# Espressomaschine.net
KiCad netlist of a schematic drawn in EAGLE
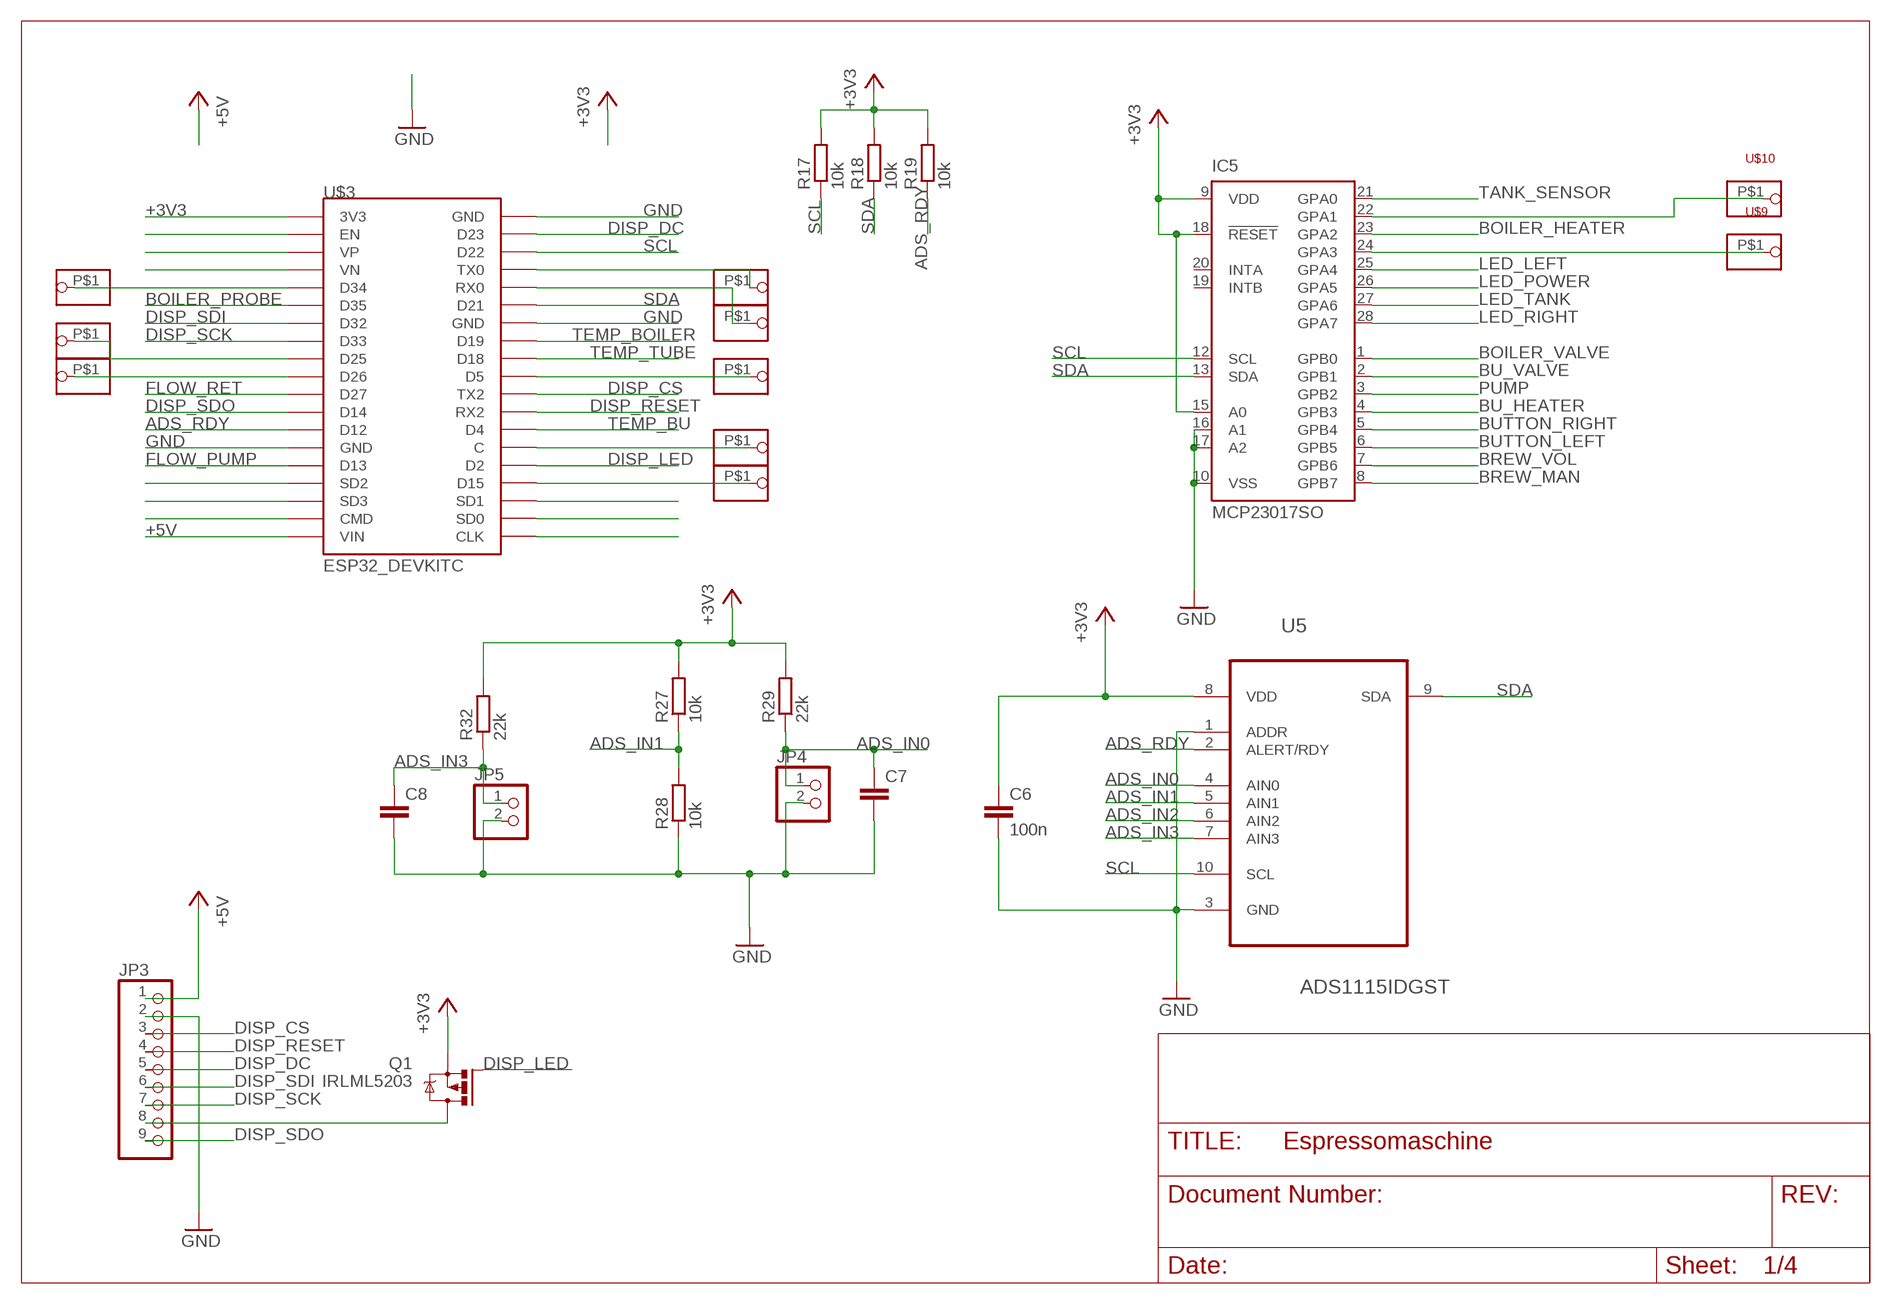
[diagram p0: schematic, sheet 1]
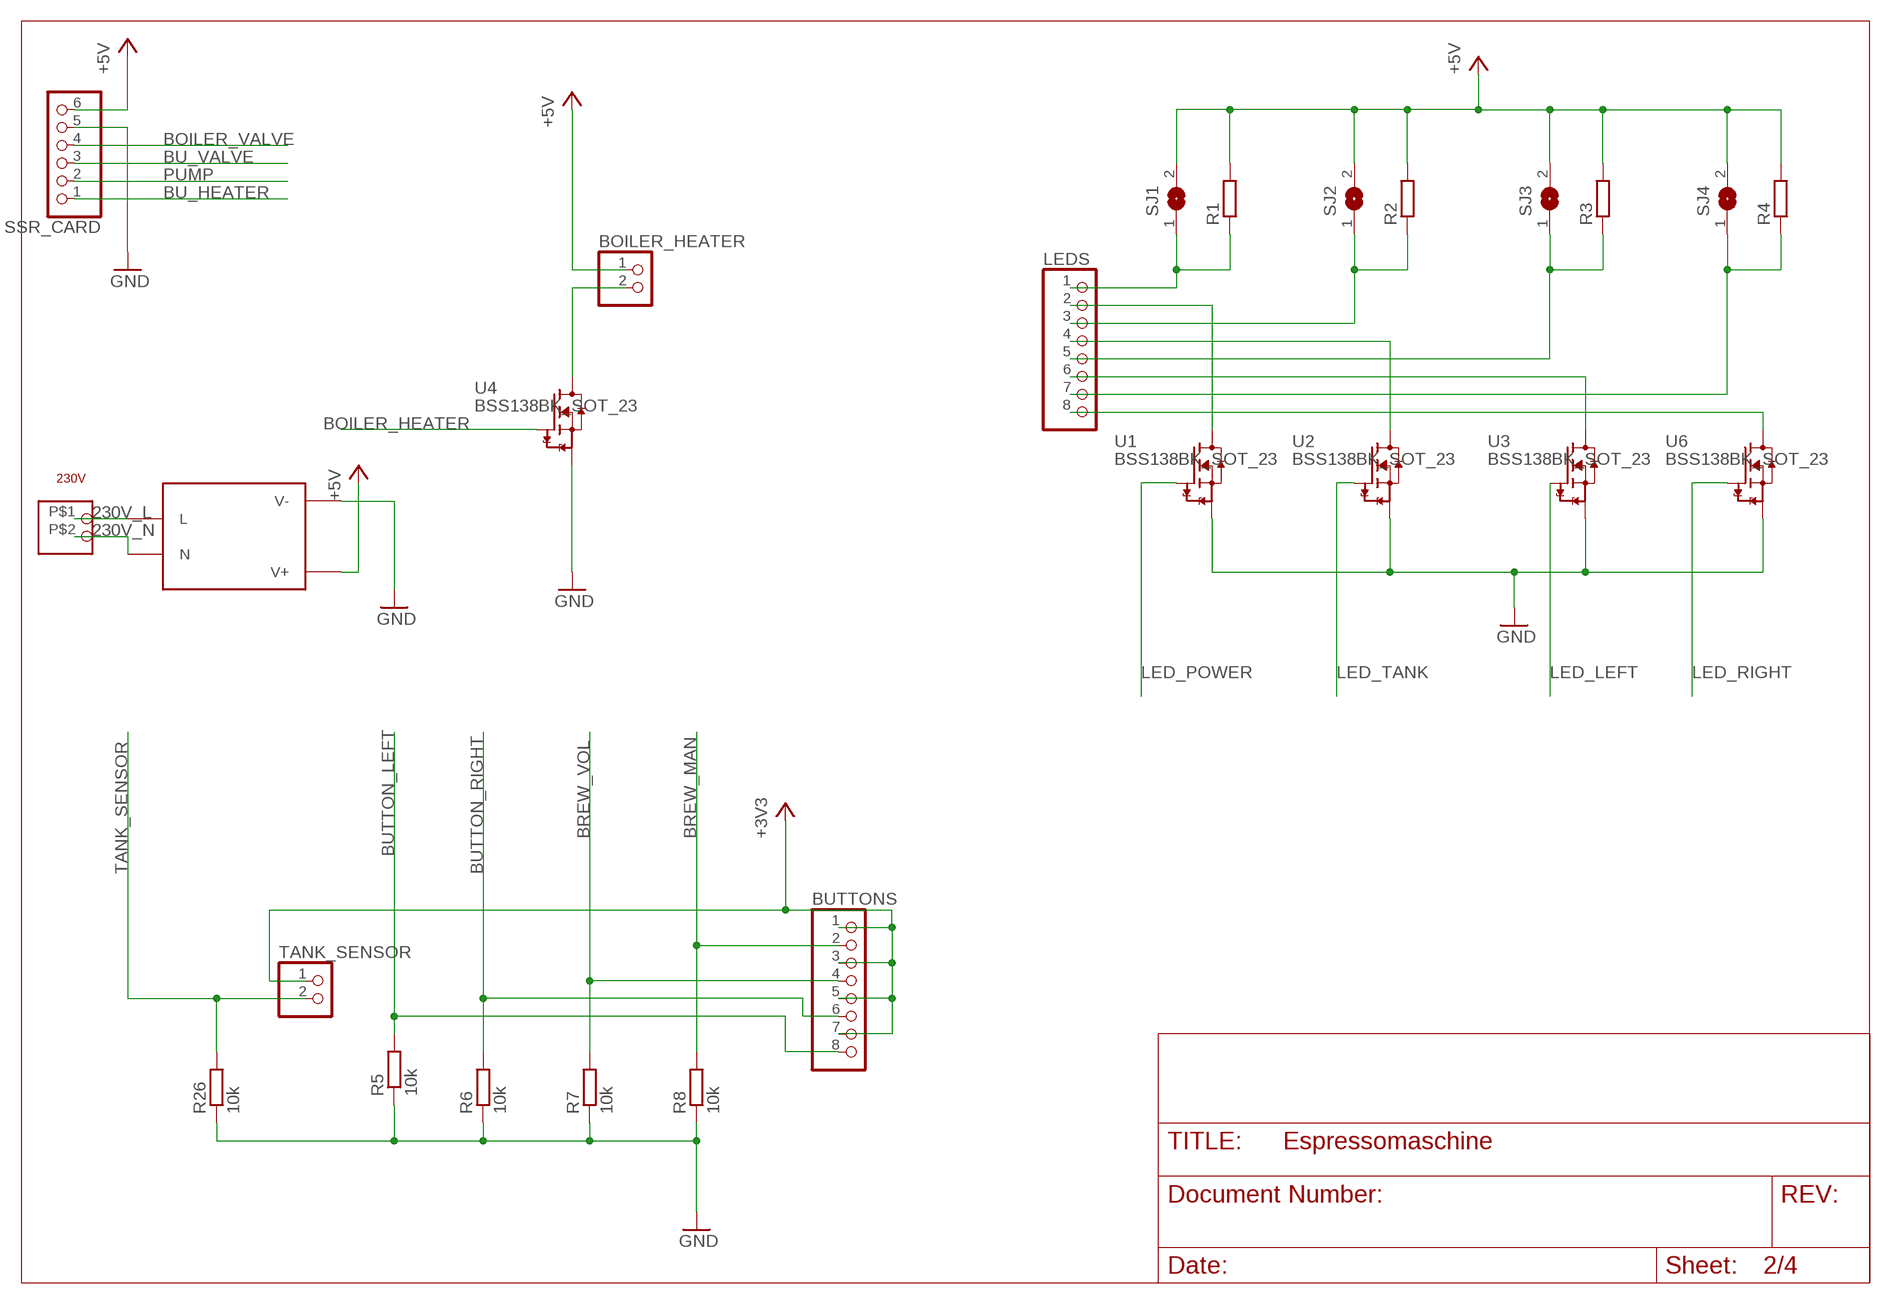
[diagram p1: schematic, sheet 2]
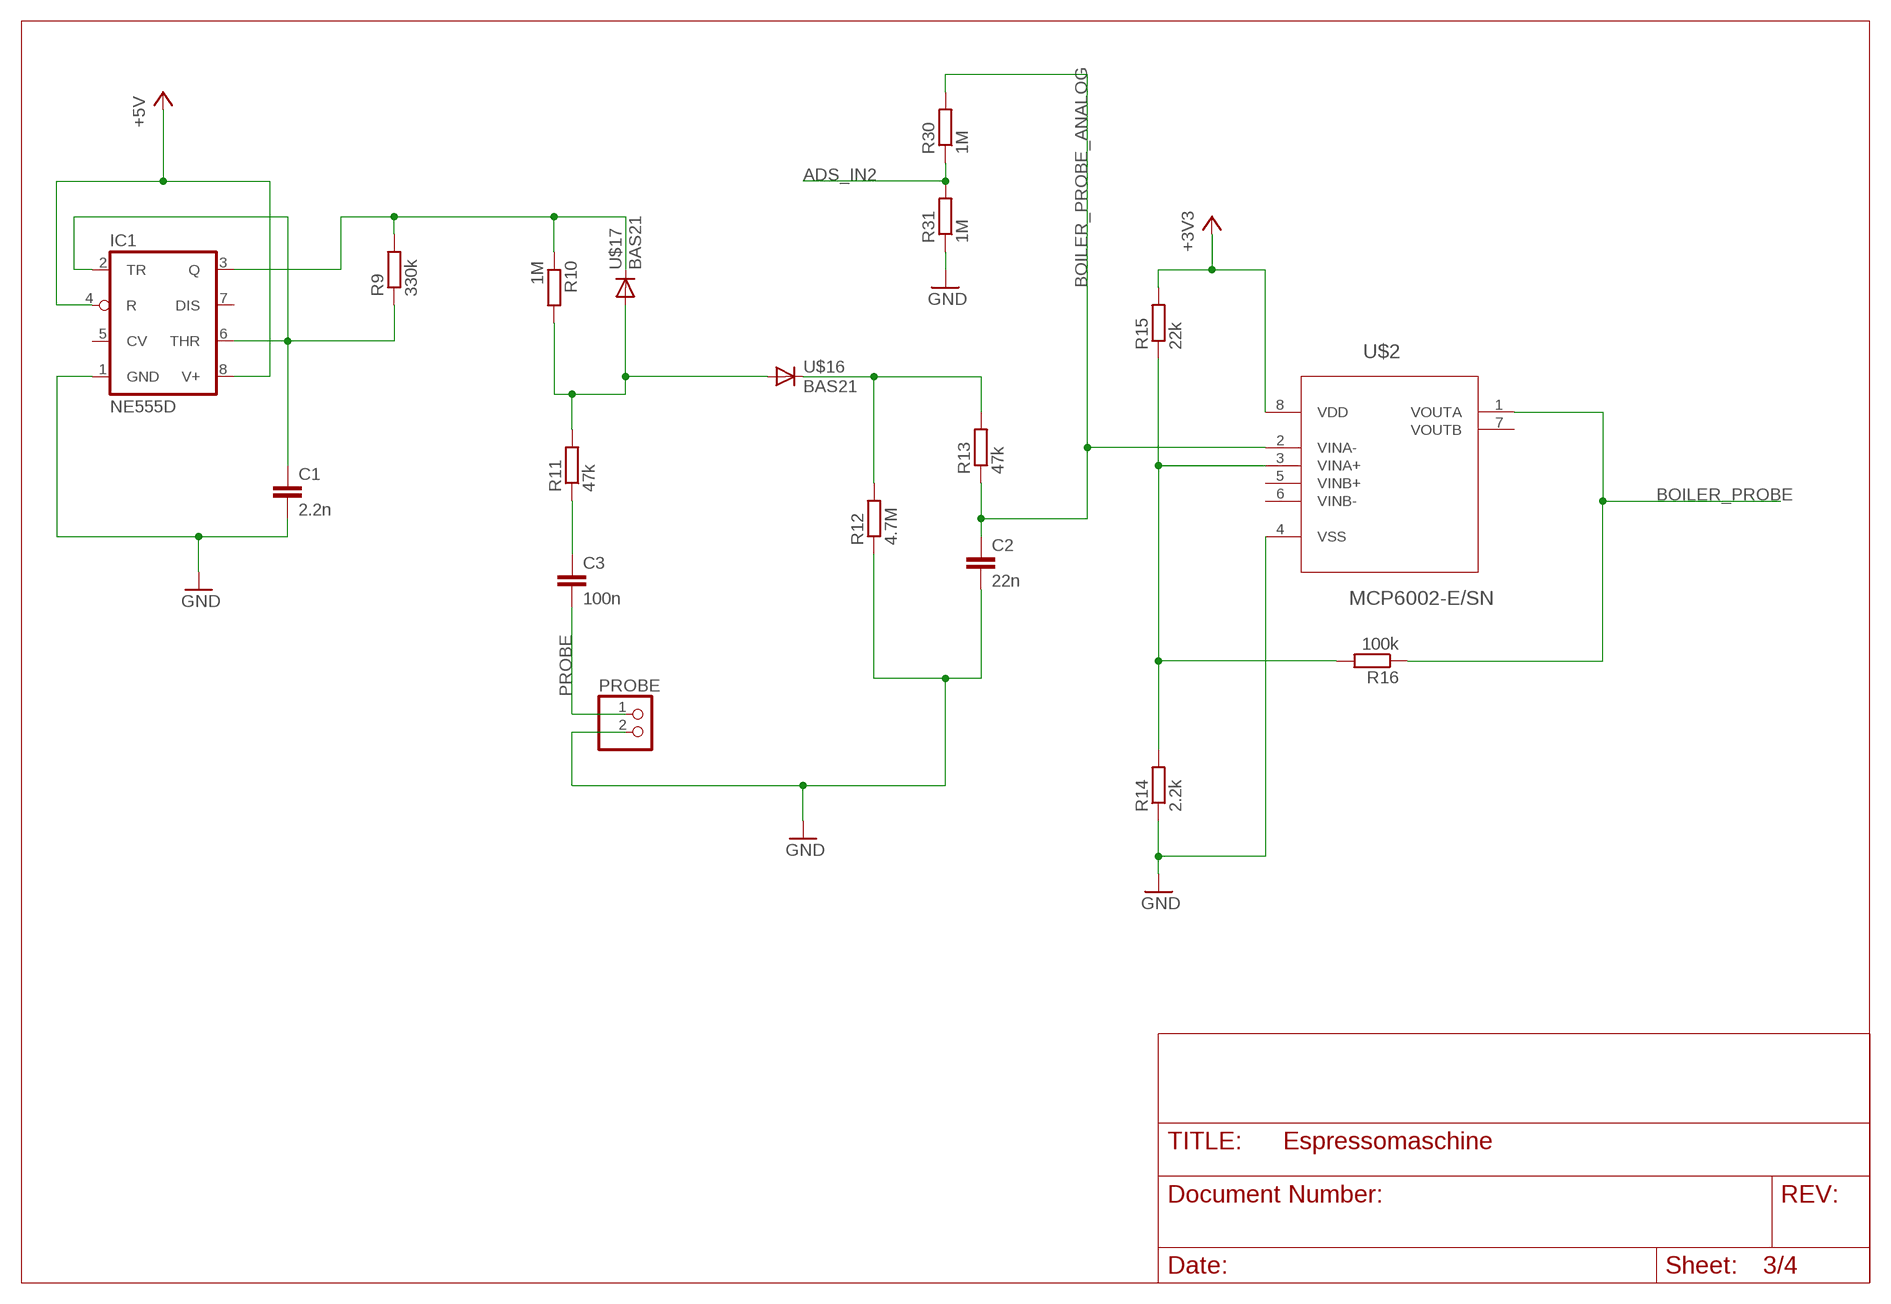
[diagram p2: schematic, sheet 3]
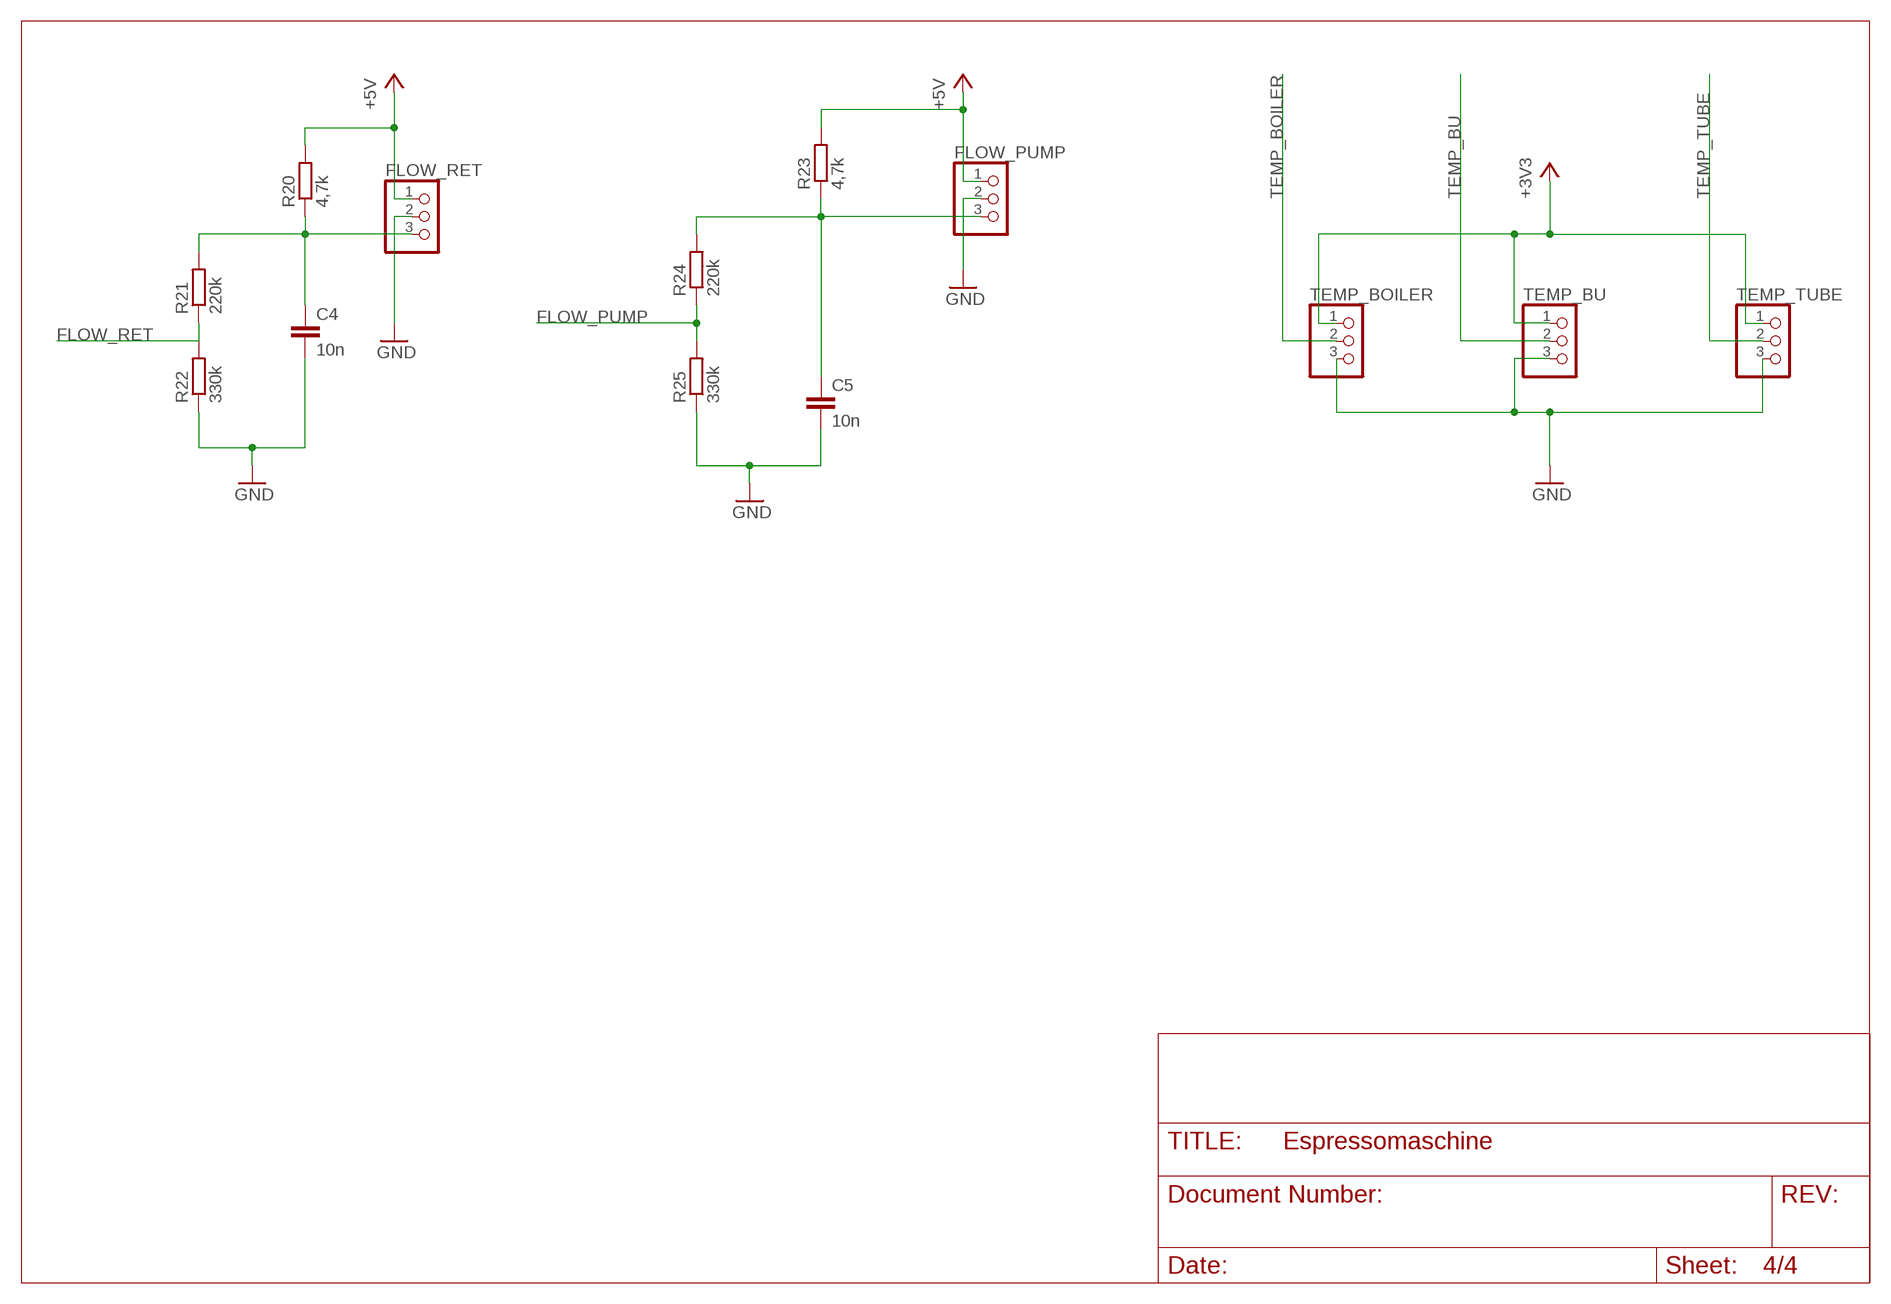
[diagram p3: schematic, sheet 4]

(export (version "E")
  (design (tool "Eeschema 10.0.6"))
  (components
    (comp (ref "230V")
      (value "1X2RM5")
      (footprint "eagle-import:1X02_RM5")
      (libsource (lib "eagle-import") (part "1X2RM5"))
    )
    (comp (ref "BOILER_HEATER")
      (value "PINHD-1X2")
      (footprint "eagle-import:1X02")
      (libsource (lib "eagle-import") (part "PINHD-1X2"))
    )
    (comp (ref "BUTTONS")
      (value "PINHD-1X8")
      (footprint "eagle-import:1X08")
      (libsource (lib "eagle-import") (part "PINHD-1X8"))
    )
    (comp (ref "LEDS")
      (value "PINHD-1X8")
      (footprint "eagle-import:1X08")
      (libsource (lib "eagle-import") (part "PINHD-1X8"))
    )
    (comp (ref "R1")
      (value "R-EU_R0603")
      (footprint "eagle-import:R0603")
      (libsource (lib "eagle-import") (part "R-EU_R0603"))
    )
    (comp (ref "R2")
      (value "R-EU_R0603")
      (footprint "eagle-import:R0603")
      (libsource (lib "eagle-import") (part "R-EU_R0603"))
    )
    (comp (ref "R3")
      (value "R-EU_R0603")
      (footprint "eagle-import:R0603")
      (libsource (lib "eagle-import") (part "R-EU_R0603"))
    )
    (comp (ref "R4")
      (value "R-EU_R0603")
      (footprint "eagle-import:R0603")
      (libsource (lib "eagle-import") (part "R-EU_R0603"))
    )
    (comp (ref "R5")
      (value "10k")
      (footprint "eagle-import:R0603")
      (libsource (lib "eagle-import") (part "R-EU_R0603"))
    )
    (comp (ref "R6")
      (value "10k")
      (footprint "eagle-import:R0603")
      (libsource (lib "eagle-import") (part "R-EU_R0603"))
    )
    (comp (ref "R7")
      (value "10k")
      (footprint "eagle-import:R0603")
      (libsource (lib "eagle-import") (part "R-EU_R0603"))
    )
    (comp (ref "R8")
      (value "10k")
      (footprint "eagle-import:R0603")
      (libsource (lib "eagle-import") (part "R-EU_R0603"))
    )
    (comp (ref "R26")
      (value "10k")
      (footprint "eagle-import:R0603")
      (libsource (lib "eagle-import") (part "R-EU_R0603"))
    )
    (comp (ref "SJ1") (value "SJ") (footprint "eagle-import:SJ") (libsource (lib "eagle-import") (part "SJ")))
    (comp (ref "SJ2") (value "SJ") (footprint "eagle-import:SJ") (libsource (lib "eagle-import") (part "SJ")))
    (comp (ref "SJ3") (value "SJ") (footprint "eagle-import:SJ") (libsource (lib "eagle-import") (part "SJ")))
    (comp (ref "SJ4") (value "SJ") (footprint "eagle-import:SJ") (libsource (lib "eagle-import") (part "SJ")))
    (comp (ref "SSR_CARD")
      (value "PINHD-1X6")
      (footprint "eagle-import:1X06")
      (libsource (lib "eagle-import") (part "PINHD-1X6"))
    )
    (comp (ref "TANK_SENSOR")
      (value "PINHD-1X2")
      (footprint "eagle-import:1X02")
      (libsource (lib "eagle-import") (part "PINHD-1X2"))
    )
    (comp (ref "U$1")
      (value "HLK-PM0X")
      (footprint "eagle-import:HLK-PM0X")
      (libsource (lib "eagle-import") (part "HLK-PM0X"))
    )
    (comp (ref "U1")
      (value "BSS138BK_SOT_23")
      (footprint "eagle-import:SOT23")
      (libsource (lib "eagle-import") (part "BSS138BK_SOT_23"))
    )
    (comp (ref "U2")
      (value "BSS138BK_SOT_23")
      (footprint "eagle-import:SOT23")
      (libsource (lib "eagle-import") (part "BSS138BK_SOT_23"))
    )
    (comp (ref "U3")
      (value "BSS138BK_SOT_23")
      (footprint "eagle-import:SOT23")
      (libsource (lib "eagle-import") (part "BSS138BK_SOT_23"))
    )
    (comp (ref "U4")
      (value "BSS138BK_SOT_23")
      (footprint "eagle-import:SOT23")
      (libsource (lib "eagle-import") (part "BSS138BK_SOT_23"))
    )
    (comp (ref "U6")
      (value "BSS138BK_SOT_23")
      (footprint "eagle-import:SOT23")
      (libsource (lib "eagle-import") (part "BSS138BK_SOT_23"))
    )
    (comp (ref "C1")
      (value "2.2n")
      (footprint "eagle-import:C0603")
      (libsource (lib "eagle-import") (part "C-EUC0603"))
    )
    (comp (ref "C2")
      (value "22n")
      (footprint "eagle-import:C0603")
      (libsource (lib "eagle-import") (part "C-EUC0603"))
    )
    (comp (ref "C3")
      (value "100n")
      (footprint "eagle-import:C0603")
      (libsource (lib "eagle-import") (part "C-EUC0603"))
    )
    (comp (ref "IC1")
      (value "NE555D")
      (footprint "eagle-import:SO08")
      (libsource (lib "eagle-import") (part "555DNE"))
    )
    (comp (ref "PROBE")
      (value "PINHD-1X2")
      (footprint "eagle-import:1X02")
      (libsource (lib "eagle-import") (part "PINHD-1X2"))
    )
    (comp (ref "R9")
      (value "330k")
      (footprint "eagle-import:R0603")
      (libsource (lib "eagle-import") (part "R-EU_R0603"))
    )
    (comp (ref "R10")
      (value "1M")
      (footprint "eagle-import:R0603")
      (libsource (lib "eagle-import") (part "R-EU_R0603"))
    )
    (comp (ref "R11")
      (value "47k")
      (footprint "eagle-import:R0603")
      (libsource (lib "eagle-import") (part "R-EU_R0603"))
    )
    (comp (ref "R12")
      (value "4.7M")
      (footprint "eagle-import:R0603")
      (libsource (lib "eagle-import") (part "R-EU_R0603"))
    )
    (comp (ref "R13")
      (value "47k")
      (footprint "eagle-import:R0603")
      (libsource (lib "eagle-import") (part "R-EU_R0603"))
    )
    (comp (ref "R14")
      (value "2.2k")
      (footprint "eagle-import:R0603")
      (libsource (lib "eagle-import") (part "R-EU_R0603"))
    )
    (comp (ref "R15")
      (value "22k")
      (footprint "eagle-import:R0603")
      (libsource (lib "eagle-import") (part "R-EU_R0603"))
    )
    (comp (ref "R16")
      (value "100k")
      (footprint "eagle-import:R0603")
      (libsource (lib "eagle-import") (part "R-EU_R0603"))
    )
    (comp (ref "R30")
      (value "1M")
      (footprint "eagle-import:R0603")
      (libsource (lib "eagle-import") (part "R-EU_R0603"))
    )
    (comp (ref "R31")
      (value "1M")
      (footprint "eagle-import:R0603")
      (libsource (lib "eagle-import") (part "R-EU_R0603"))
    )
    (comp (ref "U$2")
      (value "MCP6002-E/SN")
      (footprint "eagle-import:SOIC127P600X175-8N")
      (libsource (lib "eagle-import") (part "MCP6002-E/SN"))
    )
    (comp (ref "U$16")
      (value "BAS21")
      (footprint "eagle-import:SOT23")
      (libsource (lib "eagle-import") (part "BAS21"))
    )
    (comp (ref "U$17")
      (value "BAS21")
      (footprint "eagle-import:SOT23")
      (libsource (lib "eagle-import") (part "BAS21"))
    )
    (comp (ref "C4")
      (value "10n")
      (footprint "eagle-import:C0603")
      (libsource (lib "eagle-import") (part "C-EUC0603"))
    )
    (comp (ref "C5")
      (value "10n")
      (footprint "eagle-import:C0603")
      (libsource (lib "eagle-import") (part "C-EUC0603"))
    )
    (comp (ref "FLOW_PUMP")
      (value "PINHD-1X3")
      (footprint "eagle-import:1X03")
      (libsource (lib "eagle-import") (part "PINHD-1X3"))
    )
    (comp (ref "FLOW_RET")
      (value "PINHD-1X3")
      (footprint "eagle-import:1X03")
      (libsource (lib "eagle-import") (part "PINHD-1X3"))
    )
    (comp (ref "R20")
      (value "4,7k")
      (footprint "eagle-import:R0603")
      (libsource (lib "eagle-import") (part "R-EU_R0603"))
    )
    (comp (ref "R21")
      (value "220k")
      (footprint "eagle-import:R0603")
      (libsource (lib "eagle-import") (part "R-EU_R0603"))
    )
    (comp (ref "R22")
      (value "330k")
      (footprint "eagle-import:R0603")
      (libsource (lib "eagle-import") (part "R-EU_R0603"))
    )
    (comp (ref "R23")
      (value "4,7k")
      (footprint "eagle-import:R0603")
      (libsource (lib "eagle-import") (part "R-EU_R0603"))
    )
    (comp (ref "R24")
      (value "220k")
      (footprint "eagle-import:R0603")
      (libsource (lib "eagle-import") (part "R-EU_R0603"))
    )
    (comp (ref "R25")
      (value "330k")
      (footprint "eagle-import:R0603")
      (libsource (lib "eagle-import") (part "R-EU_R0603"))
    )
    (comp (ref "TEMP_BOILER")
      (value "PINHD-1X3")
      (footprint "eagle-import:1X03")
      (libsource (lib "eagle-import") (part "PINHD-1X3"))
    )
    (comp (ref "TEMP_BU")
      (value "PINHD-1X3")
      (footprint "eagle-import:1X03")
      (libsource (lib "eagle-import") (part "PINHD-1X3"))
    )
    (comp (ref "TEMP_TUBE")
      (value "PINHD-1X3")
      (footprint "eagle-import:1X03")
      (libsource (lib "eagle-import") (part "PINHD-1X3"))
    )
    (comp (ref "C6")
      (value "100n")
      (footprint "eagle-import:C0603")
      (libsource (lib "eagle-import") (part "C-EUC0603"))
    )
    (comp (ref "C7")
      (value "C-EUC0603")
      (footprint "eagle-import:C0603")
      (libsource (lib "eagle-import") (part "C-EUC0603"))
    )
    (comp (ref "C8")
      (value "C-EUC0603")
      (footprint "eagle-import:C0603")
      (libsource (lib "eagle-import") (part "C-EUC0603"))
    )
    (comp (ref "IC5")
      (value "MCP23017SO")
      (footprint "eagle-import:SO28W")
      (fields (field (name "MF") "MICROCHIP") (field (name "MPN") "MCP23017-E/SO"))
      (libsource (lib "eagle-import") (part "MCP23017SO"))
    )
    (comp (ref "JP3")
      (value "PINHD-1X9")
      (footprint "eagle-import:1X09")
      (libsource (lib "eagle-import") (part "PINHD-1X9"))
    )
    (comp (ref "JP4")
      (value "PINHD-1X2")
      (footprint "eagle-import:1X02")
      (libsource (lib "eagle-import") (part "PINHD-1X2"))
    )
    (comp (ref "JP5")
      (value "PINHD-1X2")
      (footprint "eagle-import:1X02")
      (libsource (lib "eagle-import") (part "PINHD-1X2"))
    )
    (comp (ref "Q1")
      (value "IRLML5203")
      (footprint "eagle-import:MICRO3")
      (libsource (lib "eagle-import") (part "IRLML5203"))
    )
    (comp (ref "R17")
      (value "10k")
      (footprint "eagle-import:R0603")
      (libsource (lib "eagle-import") (part "R-EU_R0603"))
    )
    (comp (ref "R18")
      (value "10k")
      (footprint "eagle-import:R0603")
      (libsource (lib "eagle-import") (part "R-EU_R0603"))
    )
    (comp (ref "R19")
      (value "10k")
      (footprint "eagle-import:R0603")
      (libsource (lib "eagle-import") (part "R-EU_R0603"))
    )
    (comp (ref "R27")
      (value "10k")
      (footprint "eagle-import:R0603")
      (libsource (lib "eagle-import") (part "R-EU_R0603"))
    )
    (comp (ref "R28")
      (value "10k")
      (footprint "eagle-import:R0603")
      (libsource (lib "eagle-import") (part "R-EU_R0603"))
    )
    (comp (ref "R29")
      (value "22k")
      (footprint "eagle-import:R0603")
      (libsource (lib "eagle-import") (part "R-EU_R0603"))
    )
    (comp (ref "R32")
      (value "22k")
      (footprint "eagle-import:R0603")
      (libsource (lib "eagle-import") (part "R-EU_R0603"))
    )
    (comp (ref "U$3")
      (value "ESP32_DEVKITC")
      (footprint "eagle-import:ESP32_DEVKITC")
      (libsource (lib "eagle-import") (part "ESP32_DEVKITC"))
    )
    (comp (ref "U$5")
      (value "PINHD-1X1SMD_RM1.27")
      (footprint "eagle-import:1X01_SMD_RM1.27")
      (libsource (lib "eagle-import") (part "PINHD-1X1SMD_RM1.27"))
    )
    (comp (ref "U$6")
      (value "PINHD-1X1SMD_RM1.27")
      (footprint "eagle-import:1X01_SMD_RM1.27")
      (libsource (lib "eagle-import") (part "PINHD-1X1SMD_RM1.27"))
    )
    (comp (ref "U$7")
      (value "PINHD-1X1SMD_RM1.27")
      (footprint "eagle-import:1X01_SMD_RM1.27")
      (libsource (lib "eagle-import") (part "PINHD-1X1SMD_RM1.27"))
    )
    (comp (ref "U$8")
      (value "PINHD-1X1SMD_RM1.27")
      (footprint "eagle-import:1X01_SMD_RM1.27")
      (libsource (lib "eagle-import") (part "PINHD-1X1SMD_RM1.27"))
    )
    (comp (ref "U$9")
      (value "PINHD-1X1SMD_RM1.27")
      (footprint "eagle-import:1X01_SMD_RM1.27")
      (libsource (lib "eagle-import") (part "PINHD-1X1SMD_RM1.27"))
    )
    (comp (ref "U$10")
      (value "PINHD-1X1SMD_RM1.27")
      (footprint "eagle-import:1X01_SMD_RM1.27")
      (libsource (lib "eagle-import") (part "PINHD-1X1SMD_RM1.27"))
    )
    (comp (ref "U$11")
      (value "PINHD-1X1SMD_RM1.27")
      (footprint "eagle-import:1X01_SMD_RM1.27")
      (libsource (lib "eagle-import") (part "PINHD-1X1SMD_RM1.27"))
    )
    (comp (ref "U$12")
      (value "PINHD-1X1SMD_RM1.27")
      (footprint "eagle-import:1X01_SMD_RM1.27")
      (libsource (lib "eagle-import") (part "PINHD-1X1SMD_RM1.27"))
    )
    (comp (ref "U$13")
      (value "PINHD-1X1SMD_RM1.27")
      (footprint "eagle-import:1X01_SMD_RM1.27")
      (libsource (lib "eagle-import") (part "PINHD-1X1SMD_RM1.27"))
    )
    (comp (ref "U$14")
      (value "PINHD-1X1SMD_RM1.27")
      (footprint "eagle-import:1X01_SMD_RM1.27")
      (libsource (lib "eagle-import") (part "PINHD-1X1SMD_RM1.27"))
    )
    (comp (ref "U5")
      (value "ADS1115IDGST")
      (footprint "eagle-import:SOP50P490X110-10N")
      (libsource (lib "eagle-import") (part "ADS1115IDGST"))
    )
  )
  (nets
    (net (code "1") (name "+3V3") (class "Default")
      (node (ref "BUTTONS") (pin "1") (pinfunction "1_1") (pintype "passive"))
      (node (ref "BUTTONS") (pin "3") (pinfunction "3_3") (pintype "passive"))
      (node (ref "BUTTONS") (pin "5") (pinfunction "5_5") (pintype "passive"))
      (node (ref "BUTTONS") (pin "7") (pinfunction "7_7") (pintype "passive"))
      (node (ref "C6") (pin "1") (pinfunction "1_1") (pintype "passive"))
      (node (ref "IC5") (pin "15") (pinfunction "A0_15") (pintype "input"))
      (node (ref "IC5") (pin "18") (pinfunction "~{RESET}_18") (pintype "input"))
      (node (ref "IC5") (pin "9") (pinfunction "VDD_9") (pintype "power_in"))
      (node (ref "Q1") (pin "2") (pinfunction "S_2") (pintype "passive"))
      (node (ref "R15") (pin "2") (pinfunction "2_2") (pintype "passive"))
      (node (ref "R17") (pin "2") (pinfunction "2_2") (pintype "passive"))
      (node (ref "R18") (pin "2") (pinfunction "2_2") (pintype "passive"))
      (node (ref "R19") (pin "2") (pinfunction "2_2") (pintype "passive"))
      (node (ref "R27") (pin "2") (pinfunction "2_2") (pintype "passive"))
      (node (ref "R29") (pin "2") (pinfunction "2_2") (pintype "passive"))
      (node (ref "R32") (pin "2") (pinfunction "2_2") (pintype "passive"))
      (node (ref "TANK_SENSOR") (pin "1") (pinfunction "1_1") (pintype "passive"))
      (node (ref "TEMP_BOILER") (pin "1") (pinfunction "1_1") (pintype "passive"))
      (node (ref "TEMP_BU") (pin "1") (pinfunction "1_1") (pintype "passive"))
      (node (ref "TEMP_TUBE") (pin "1") (pinfunction "1_1") (pintype "passive"))
      (node (ref "U$2") (pin "8") (pinfunction "VDD_8") (pintype "power_in"))
      (node (ref "U$3") (pin "3V3") (pinfunction "3V3_3V3") (pintype "bidirectional"))
      (node (ref "U5") (pin "8") (pinfunction "VDD_8") (pintype "power_in"))
    )
    (net (code "2") (name "+5V") (class "Default")
      (node (ref "BOILER_HEATER") (pin "1") (pinfunction "1_1") (pintype "passive"))
      (node (ref "FLOW_PUMP") (pin "1") (pinfunction "1_1") (pintype "passive"))
      (node (ref "FLOW_RET") (pin "1") (pinfunction "1_1") (pintype "passive"))
      (node (ref "IC1") (pin "4") (pinfunction "R_4") (pintype "input"))
      (node (ref "IC1") (pin "8") (pinfunction "V+_8") (pintype "power_in"))
      (node (ref "JP3") (pin "1") (pinfunction "1_1") (pintype "passive"))
      (node (ref "R1") (pin "2") (pinfunction "2_2") (pintype "passive"))
      (node (ref "R2") (pin "2") (pinfunction "2_2") (pintype "passive"))
      (node (ref "R20") (pin "2") (pinfunction "2_2") (pintype "passive"))
      (node (ref "R23") (pin "2") (pinfunction "2_2") (pintype "passive"))
      (node (ref "R3") (pin "2") (pinfunction "2_2") (pintype "passive"))
      (node (ref "R4") (pin "2") (pinfunction "2_2") (pintype "passive"))
      (node (ref "SJ1") (pin "2") (pinfunction "2_2") (pintype "passive"))
      (node (ref "SJ2") (pin "2") (pinfunction "2_2") (pintype "passive"))
      (node (ref "SJ3") (pin "2") (pinfunction "2_2") (pintype "passive"))
      (node (ref "SJ4") (pin "2") (pinfunction "2_2") (pintype "passive"))
      (node (ref "SSR_CARD") (pin "6") (pinfunction "6_6") (pintype "passive"))
      (node (ref "U$1") (pin "V+") (pinfunction "V+_V+") (pintype "bidirectional"))
      (node (ref "U$3") (pin "VIN") (pinfunction "VIN_VIN") (pintype "bidirectional"))
    )
    (net (code "3") (name "230V_L") (class "Default")
      (node (ref "230V") (pin "P$1") (pinfunction "1_P$1") (pintype "bidirectional"))
      (node (ref "U$1") (pin "L") (pinfunction "L_L") (pintype "bidirectional"))
    )
    (net (code "4") (name "230V_N") (class "Default")
      (node (ref "230V") (pin "P$2") (pinfunction "2_P$2") (pintype "bidirectional"))
      (node (ref "U$1") (pin "N") (pinfunction "N_N") (pintype "bidirectional"))
    )
    (net (code "5") (name "ADS_IN0") (class "Default")
      (node (ref "C7") (pin "1") (pinfunction "1_1") (pintype "passive"))
      (node (ref "JP4") (pin "1") (pinfunction "1_1") (pintype "passive"))
      (node (ref "R29") (pin "1") (pinfunction "1_1") (pintype "passive"))
      (node (ref "U5") (pin "4") (pinfunction "AIN0_4") (pintype "input"))
    )
    (net (code "6") (name "ADS_IN1") (class "Default")
      (node (ref "R27") (pin "1") (pinfunction "1_1") (pintype "passive"))
      (node (ref "R28") (pin "2") (pinfunction "2_2") (pintype "passive"))
      (node (ref "U5") (pin "5") (pinfunction "AIN1_5") (pintype "input"))
    )
    (net (code "7") (name "ADS_IN2") (class "Default")
      (node (ref "R30") (pin "1") (pinfunction "1_1") (pintype "passive"))
      (node (ref "R31") (pin "2") (pinfunction "2_2") (pintype "passive"))
      (node (ref "U5") (pin "6") (pinfunction "AIN2_6") (pintype "input"))
    )
    (net (code "8") (name "ADS_IN3") (class "Default")
      (node (ref "C8") (pin "1") (pinfunction "1_1") (pintype "passive"))
      (node (ref "JP5") (pin "1") (pinfunction "1_1") (pintype "passive"))
      (node (ref "R32") (pin "1") (pinfunction "1_1") (pintype "passive"))
      (node (ref "U5") (pin "7") (pinfunction "AIN3_7") (pintype "input"))
    )
    (net (code "9") (name "ADS_RDY") (class "Default")
      (node (ref "R19") (pin "1") (pinfunction "1_1") (pintype "passive"))
      (node (ref "U$3") (pin "D12") (pinfunction "D12_D12") (pintype "bidirectional"))
      (node (ref "U5") (pin "2") (pinfunction "ALERT/RDY_2") (pintype "input"))
    )
    (net (code "10") (name "BOILER_HEATER") (class "Default")
      (node (ref "IC5") (pin "23") (pinfunction "GPA2_23") (pintype "bidirectional"))
      (node (ref "U4") (pin "1") (pinfunction "G_1") (pintype "passive"))
    )
    (net (code "11") (name "BOILER_PROBE") (class "Default")
      (node (ref "R16") (pin "1") (pinfunction "1_1") (pintype "passive"))
      (node (ref "U$2") (pin "1") (pinfunction "VOUTA_1") (pintype "output"))
      (node (ref "U$3") (pin "D35") (pinfunction "D35_D35") (pintype "bidirectional"))
    )
    (net (code "12") (name "BOILER_PROBE_ANALOG") (class "Default")
      (node (ref "C2") (pin "1") (pinfunction "1_1") (pintype "passive"))
      (node (ref "R13") (pin "1") (pinfunction "1_1") (pintype "passive"))
      (node (ref "R30") (pin "2") (pinfunction "2_2") (pintype "passive"))
      (node (ref "U$2") (pin "2") (pinfunction "VINA-_2") (pintype "input"))
    )
    (net (code "13") (name "BOILER_VALVE") (class "Default")
      (node (ref "IC5") (pin "1") (pinfunction "GPB0_1") (pintype "bidirectional"))
      (node (ref "SSR_CARD") (pin "4") (pinfunction "4_4") (pintype "passive"))
    )
    (net (code "14") (name "BREW_MAN") (class "Default")
      (node (ref "BUTTONS") (pin "2") (pinfunction "2_2") (pintype "passive"))
      (node (ref "IC5") (pin "8") (pinfunction "GPB7_8") (pintype "bidirectional"))
      (node (ref "R8") (pin "2") (pinfunction "2_2") (pintype "passive"))
    )
    (net (code "15") (name "BREW_VOL") (class "Default")
      (node (ref "BUTTONS") (pin "4") (pinfunction "4_4") (pintype "passive"))
      (node (ref "IC5") (pin "7") (pinfunction "GPB6_7") (pintype "bidirectional"))
      (node (ref "R7") (pin "2") (pinfunction "2_2") (pintype "passive"))
    )
    (net (code "16") (name "BUTTON_LEFT") (class "Default")
      (node (ref "BUTTONS") (pin "8") (pinfunction "8_8") (pintype "passive"))
      (node (ref "IC5") (pin "6") (pinfunction "GPB5_6") (pintype "bidirectional"))
      (node (ref "R5") (pin "2") (pinfunction "2_2") (pintype "passive"))
    )
    (net (code "17") (name "BUTTON_RIGHT") (class "Default")
      (node (ref "BUTTONS") (pin "6") (pinfunction "6_6") (pintype "passive"))
      (node (ref "IC5") (pin "5") (pinfunction "GPB4_5") (pintype "bidirectional"))
      (node (ref "R6") (pin "2") (pinfunction "2_2") (pintype "passive"))
    )
    (net (code "18") (name "BU_HEATER") (class "Default")
      (node (ref "IC5") (pin "4") (pinfunction "GPB3_4") (pintype "bidirectional"))
      (node (ref "SSR_CARD") (pin "1") (pinfunction "1_1") (pintype "passive"))
    )
    (net (code "19") (name "BU_VALVE") (class "Default")
      (node (ref "IC5") (pin "2") (pinfunction "GPB1_2") (pintype "bidirectional"))
      (node (ref "SSR_CARD") (pin "3") (pinfunction "3_3") (pintype "passive"))
    )
    (net (code "20") (name "DISP_CS") (class "Default")
      (node (ref "JP3") (pin "3") (pinfunction "3_3") (pintype "passive"))
      (node (ref "U$3") (pin "TX2") (pinfunction "TX2_TX2") (pintype "bidirectional"))
    )
    (net (code "21") (name "DISP_DC") (class "Default")
      (node (ref "JP3") (pin "5") (pinfunction "5_5") (pintype "passive"))
      (node (ref "U$3") (pin "D23") (pinfunction "D23_D23") (pintype "bidirectional"))
    )
    (net (code "22") (name "DISP_LED") (class "Default")
      (node (ref "Q1") (pin "1") (pinfunction "G_1") (pintype "passive"))
      (node (ref "U$3") (pin "D2") (pinfunction "D2_D2") (pintype "bidirectional"))
    )
    (net (code "23") (name "DISP_RESET") (class "Default")
      (node (ref "JP3") (pin "4") (pinfunction "4_4") (pintype "passive"))
      (node (ref "U$3") (pin "RX2") (pinfunction "RX2_RX2") (pintype "bidirectional"))
    )
    (net (code "24") (name "DISP_SCK") (class "Default")
      (node (ref "JP3") (pin "7") (pinfunction "7_7") (pintype "passive"))
      (node (ref "U$3") (pin "D33") (pinfunction "D33_D33") (pintype "bidirectional"))
    )
    (net (code "25") (name "DISP_SDI") (class "Default")
      (node (ref "JP3") (pin "6") (pinfunction "6_6") (pintype "passive"))
      (node (ref "U$3") (pin "D32") (pinfunction "D32_D32") (pintype "bidirectional"))
    )
    (net (code "26") (name "DISP_SDO") (class "Default")
      (node (ref "JP3") (pin "9") (pinfunction "9_9") (pintype "passive"))
      (node (ref "U$3") (pin "D14") (pinfunction "D14_D14") (pintype "bidirectional"))
    )
    (net (code "27") (name "FLOW_PUMP") (class "Default")
      (node (ref "R24") (pin "1") (pinfunction "1_1") (pintype "passive"))
      (node (ref "R25") (pin "2") (pinfunction "2_2") (pintype "passive"))
      (node (ref "U$3") (pin "D13") (pinfunction "D13_D13") (pintype "bidirectional"))
    )
    (net (code "28") (name "FLOW_RET") (class "Default")
      (node (ref "R21") (pin "1") (pinfunction "1_1") (pintype "passive"))
      (node (ref "R22") (pin "2") (pinfunction "2_2") (pintype "passive"))
      (node (ref "U$3") (pin "D27") (pinfunction "D27_D27") (pintype "bidirectional"))
    )
    (net (code "29") (name "GND") (class "Default")
      (node (ref "C1") (pin "2") (pinfunction "2_2") (pintype "passive"))
      (node (ref "C2") (pin "2") (pinfunction "2_2") (pintype "passive"))
      (node (ref "C4") (pin "2") (pinfunction "2_2") (pintype "passive"))
      (node (ref "C5") (pin "2") (pinfunction "2_2") (pintype "passive"))
      (node (ref "C6") (pin "2") (pinfunction "2_2") (pintype "passive"))
      (node (ref "C7") (pin "2") (pinfunction "2_2") (pintype "passive"))
      (node (ref "C8") (pin "2") (pinfunction "2_2") (pintype "passive"))
      (node (ref "FLOW_PUMP") (pin "2") (pinfunction "2_2") (pintype "passive"))
      (node (ref "FLOW_RET") (pin "2") (pinfunction "2_2") (pintype "passive"))
      (node (ref "IC1") (pin "1") (pinfunction "GND_1") (pintype "power_in"))
      (node (ref "IC5") (pin "10") (pinfunction "VSS_10") (pintype "power_in"))
      (node (ref "IC5") (pin "16") (pinfunction "A1_16") (pintype "input"))
      (node (ref "IC5") (pin "17") (pinfunction "A2_17") (pintype "input"))
      (node (ref "JP3") (pin "2") (pinfunction "2_2") (pintype "passive"))
      (node (ref "JP4") (pin "2") (pinfunction "2_2") (pintype "passive"))
      (node (ref "JP5") (pin "2") (pinfunction "2_2") (pintype "passive"))
      (node (ref "PROBE") (pin "2") (pinfunction "2_2") (pintype "passive"))
      (node (ref "R12") (pin "1") (pinfunction "1_1") (pintype "passive"))
      (node (ref "R14") (pin "1") (pinfunction "1_1") (pintype "passive"))
      (node (ref "R22") (pin "1") (pinfunction "1_1") (pintype "passive"))
      (node (ref "R25") (pin "1") (pinfunction "1_1") (pintype "passive"))
      (node (ref "R26") (pin "1") (pinfunction "1_1") (pintype "passive"))
      (node (ref "R28") (pin "1") (pinfunction "1_1") (pintype "passive"))
      (node (ref "R31") (pin "1") (pinfunction "1_1") (pintype "passive"))
      (node (ref "R5") (pin "1") (pinfunction "1_1") (pintype "passive"))
      (node (ref "R6") (pin "1") (pinfunction "1_1") (pintype "passive"))
      (node (ref "R7") (pin "1") (pinfunction "1_1") (pintype "passive"))
      (node (ref "R8") (pin "1") (pinfunction "1_1") (pintype "passive"))
      (node (ref "SSR_CARD") (pin "5") (pinfunction "5_5") (pintype "passive"))
      (node (ref "TEMP_BOILER") (pin "3") (pinfunction "3_3") (pintype "passive"))
      (node (ref "TEMP_BU") (pin "3") (pinfunction "3_3") (pintype "passive"))
      (node (ref "TEMP_TUBE") (pin "3") (pinfunction "3_3") (pintype "passive"))
      (node (ref "U$1") (pin "V-") (pinfunction "V-_V-") (pintype "bidirectional"))
      (node (ref "U$2") (pin "4") (pinfunction "VSS_4") (pintype "power_in"))
      (node (ref "U$3") (pin "GND@1") (pinfunction "GND_GND@1") (pintype "bidirectional"))
      (node (ref "U$3") (pin "GND@2") (pinfunction "GND_GND@2") (pintype "bidirectional"))
      (node (ref "U$3") (pin "GND@3") (pinfunction "GND_GND@3") (pintype "bidirectional"))
      (node (ref "U1") (pin "2") (pinfunction "S_2") (pintype "passive"))
      (node (ref "U2") (pin "2") (pinfunction "S_2") (pintype "passive"))
      (node (ref "U3") (pin "2") (pinfunction "S_2") (pintype "passive"))
      (node (ref "U4") (pin "2") (pinfunction "S_2") (pintype "passive"))
      (node (ref "U5") (pin "1") (pinfunction "ADDR_1") (pintype "input"))
      (node (ref "U5") (pin "3") (pinfunction "GND_3") (pintype "passive"))
      (node (ref "U6") (pin "2") (pinfunction "S_2") (pintype "passive"))
    )
    (net (code "30") (name "LED_LEFT") (class "Default")
      (node (ref "IC5") (pin "25") (pinfunction "GPA4_25") (pintype "bidirectional"))
      (node (ref "U3") (pin "1") (pinfunction "G_1") (pintype "passive"))
    )
    (net (code "31") (name "LED_POWER") (class "Default")
      (node (ref "IC5") (pin "26") (pinfunction "GPA5_26") (pintype "bidirectional"))
      (node (ref "U1") (pin "1") (pinfunction "G_1") (pintype "passive"))
    )
    (net (code "32") (name "LED_RIGHT") (class "Default")
      (node (ref "IC5") (pin "28") (pinfunction "GPA7_28") (pintype "bidirectional"))
      (node (ref "U6") (pin "1") (pinfunction "G_1") (pintype "passive"))
    )
    (net (code "33") (name "LED_TANK") (class "Default")
      (node (ref "IC5") (pin "27") (pinfunction "GPA6_27") (pintype "bidirectional"))
      (node (ref "U2") (pin "1") (pinfunction "G_1") (pintype "passive"))
    )
    (net (code "34") (name "Net-(C3-Pad1)") (class "Default")
      (node (ref "C3") (pin "1") (pinfunction "1_1") (pintype "passive"))
      (node (ref "R11") (pin "1") (pinfunction "1_1") (pintype "passive"))
    )
    (net (code "35") (name "Net-(C4-Pad1)") (class "Default")
      (node (ref "C4") (pin "1") (pinfunction "1_1") (pintype "passive"))
      (node (ref "FLOW_RET") (pin "3") (pinfunction "3_3") (pintype "passive"))
      (node (ref "R20") (pin "1") (pinfunction "1_1") (pintype "passive"))
      (node (ref "R21") (pin "2") (pinfunction "2_2") (pintype "passive"))
    )
    (net (code "36") (name "Net-(C5-Pad1)") (class "Default")
      (node (ref "C5") (pin "1") (pinfunction "1_1") (pintype "passive"))
      (node (ref "FLOW_PUMP") (pin "3") (pinfunction "3_3") (pintype "passive"))
      (node (ref "R23") (pin "1") (pinfunction "1_1") (pintype "passive"))
      (node (ref "R24") (pin "2") (pinfunction "2_2") (pintype "passive"))
    )
    (net (code "37") (name "Net-(IC1-Q)") (class "Default")
      (node (ref "IC1") (pin "3") (pinfunction "Q_3") (pintype "output"))
      (node (ref "R10") (pin "1") (pinfunction "1_1") (pintype "passive"))
      (node (ref "R9") (pin "2") (pinfunction "2_2") (pintype "passive"))
      (node (ref "U$17") (pin "3") (pinfunction "C_3") (pintype "passive"))
    )
    (net (code "38") (name "Net-(IC1-THR)") (class "Default")
      (node (ref "C1") (pin "1") (pinfunction "1_1") (pintype "passive"))
      (node (ref "IC1") (pin "2") (pinfunction "TR_2") (pintype "input"))
      (node (ref "IC1") (pin "6") (pinfunction "THR_6") (pintype "input"))
      (node (ref "R9") (pin "1") (pinfunction "1_1") (pintype "passive"))
    )
    (net (code "39") (name "Net-(IC5-GPA1)") (class "Default")
      (node (ref "IC5") (pin "22") (pinfunction "GPA1_22") (pintype "bidirectional"))
      (node (ref "U$10") (pin "P$1") (pinfunction "1_P$1") (pintype "bidirectional"))
    )
    (net (code "40") (name "Net-(IC5-GPA3)") (class "Default")
      (node (ref "IC5") (pin "24") (pinfunction "GPA3_24") (pintype "bidirectional"))
      (node (ref "U$9") (pin "P$1") (pinfunction "1_P$1") (pintype "bidirectional"))
    )
    (net (code "41") (name "Net-(LEDS-Pad1)") (class "Default")
      (node (ref "LEDS") (pin "1") (pinfunction "1_1") (pintype "passive"))
      (node (ref "R1") (pin "1") (pinfunction "1_1") (pintype "passive"))
      (node (ref "SJ1") (pin "1") (pinfunction "1_1") (pintype "passive"))
    )
    (net (code "42") (name "Net-(LEDS-Pad3)") (class "Default")
      (node (ref "LEDS") (pin "3") (pinfunction "3_3") (pintype "passive"))
      (node (ref "R2") (pin "1") (pinfunction "1_1") (pintype "passive"))
      (node (ref "SJ2") (pin "1") (pinfunction "1_1") (pintype "passive"))
    )
    (net (code "43") (name "Net-(LEDS-Pad5)") (class "Default")
      (node (ref "LEDS") (pin "5") (pinfunction "5_5") (pintype "passive"))
      (node (ref "R3") (pin "1") (pinfunction "1_1") (pintype "passive"))
      (node (ref "SJ3") (pin "1") (pinfunction "1_1") (pintype "passive"))
    )
    (net (code "44") (name "Net-(LEDS-Pad7)") (class "Default")
      (node (ref "LEDS") (pin "7") (pinfunction "7_7") (pintype "passive"))
      (node (ref "R4") (pin "1") (pinfunction "1_1") (pintype "passive"))
      (node (ref "SJ4") (pin "1") (pinfunction "1_1") (pintype "passive"))
    )
    (net (code "45") (name "Net-(Q1-D)") (class "Default")
      (node (ref "JP3") (pin "8") (pinfunction "8_8") (pintype "passive"))
      (node (ref "Q1") (pin "3") (pinfunction "D_3") (pintype "passive"))
    )
    (net (code "46") (name "Net-(U$2-VINA+)") (class "Default")
      (node (ref "R14") (pin "2") (pinfunction "2_2") (pintype "passive"))
      (node (ref "R15") (pin "1") (pinfunction "1_1") (pintype "passive"))
      (node (ref "R16") (pin "2") (pinfunction "2_2") (pintype "passive"))
      (node (ref "U$2") (pin "3") (pinfunction "VINA+_3") (pintype "input"))
    )
    (net (code "47") (name "Net-(U$5-1)") (class "Default")
      (node (ref "U$3") (pin "TX0") (pinfunction "TX0_TX0") (pintype "bidirectional"))
      (node (ref "U$5") (pin "P$1") (pinfunction "1_P$1") (pintype "bidirectional"))
    )
    (net (code "48") (name "Net-(U$6-1)") (class "Default")
      (node (ref "U$3") (pin "D5") (pinfunction "D5_D5") (pintype "bidirectional"))
      (node (ref "U$6") (pin "P$1") (pinfunction "1_P$1") (pintype "bidirectional"))
    )
    (net (code "49") (name "Net-(U$7-1)") (class "Default")
      (node (ref "U$3") (pin "C") (pinfunction "C_C") (pintype "bidirectional"))
      (node (ref "U$7") (pin "P$1") (pinfunction "1_P$1") (pintype "bidirectional"))
    )
    (net (code "50") (name "Net-(U$8-1)") (class "Default")
      (node (ref "U$3") (pin "D15") (pinfunction "D15_D15") (pintype "bidirectional"))
      (node (ref "U$8") (pin "P$1") (pinfunction "1_P$1") (pintype "bidirectional"))
    )
    (net (code "51") (name "Net-(U$11-1)") (class "Default")
      (node (ref "U$11") (pin "P$1") (pinfunction "1_P$1") (pintype "bidirectional"))
      (node (ref "U$3") (pin "RX0") (pinfunction "RX0_RX0") (pintype "bidirectional"))
    )
    (net (code "52") (name "Net-(U$12-1)") (class "Default")
      (node (ref "U$12") (pin "P$1") (pinfunction "1_P$1") (pintype "bidirectional"))
      (node (ref "U$3") (pin "D34") (pinfunction "D34_D34") (pintype "bidirectional"))
    )
    (net (code "53") (name "Net-(U$13-1)") (class "Default")
      (node (ref "U$13") (pin "P$1") (pinfunction "1_P$1") (pintype "bidirectional"))
      (node (ref "U$3") (pin "D25") (pinfunction "D25_D25") (pintype "bidirectional"))
    )
    (net (code "54") (name "Net-(U$14-1)") (class "Default")
      (node (ref "U$14") (pin "P$1") (pinfunction "1_P$1") (pintype "bidirectional"))
      (node (ref "U$3") (pin "D26") (pinfunction "D26_D26") (pintype "bidirectional"))
    )
    (net (code "55") (name "Net-(U$16-A)") (class "Default")
      (node (ref "R10") (pin "2") (pinfunction "2_2") (pintype "passive"))
      (node (ref "R11") (pin "2") (pinfunction "2_2") (pintype "passive"))
      (node (ref "U$16") (pin "1") (pinfunction "A_1") (pintype "passive"))
      (node (ref "U$17") (pin "1") (pinfunction "A_1") (pintype "passive"))
    )
    (net (code "56") (name "Net-(U$16-C)") (class "Default")
      (node (ref "R12") (pin "2") (pinfunction "2_2") (pintype "passive"))
      (node (ref "R13") (pin "2") (pinfunction "2_2") (pintype "passive"))
      (node (ref "U$16") (pin "3") (pinfunction "C_3") (pintype "passive"))
    )
    (net (code "57") (name "Net-(U1-D)") (class "Default")
      (node (ref "LEDS") (pin "2") (pinfunction "2_2") (pintype "passive"))
      (node (ref "U1") (pin "3") (pinfunction "D_3") (pintype "passive"))
    )
    (net (code "58") (name "Net-(U2-D)") (class "Default")
      (node (ref "LEDS") (pin "4") (pinfunction "4_4") (pintype "passive"))
      (node (ref "U2") (pin "3") (pinfunction "D_3") (pintype "passive"))
    )
    (net (code "59") (name "Net-(U3-D)") (class "Default")
      (node (ref "LEDS") (pin "6") (pinfunction "6_6") (pintype "passive"))
      (node (ref "U3") (pin "3") (pinfunction "D_3") (pintype "passive"))
    )
    (net (code "60") (name "Net-(U4-D)") (class "Default")
      (node (ref "BOILER_HEATER") (pin "2") (pinfunction "2_2") (pintype "passive"))
      (node (ref "U4") (pin "3") (pinfunction "D_3") (pintype "passive"))
    )
    (net (code "61") (name "Net-(U6-D)") (class "Default")
      (node (ref "LEDS") (pin "8") (pinfunction "8_8") (pintype "passive"))
      (node (ref "U6") (pin "3") (pinfunction "D_3") (pintype "passive"))
    )
    (net (code "62") (name "PROBE") (class "Default")
      (node (ref "C3") (pin "2") (pinfunction "2_2") (pintype "passive"))
      (node (ref "PROBE") (pin "1") (pinfunction "1_1") (pintype "passive"))
    )
    (net (code "63") (name "PUMP") (class "Default")
      (node (ref "IC5") (pin "3") (pinfunction "GPB2_3") (pintype "bidirectional"))
      (node (ref "SSR_CARD") (pin "2") (pinfunction "2_2") (pintype "passive"))
    )
    (net (code "64") (name "SCL") (class "Default")
      (node (ref "IC5") (pin "12") (pinfunction "SCL_12") (pintype "input"))
      (node (ref "R17") (pin "1") (pinfunction "1_1") (pintype "passive"))
      (node (ref "U$3") (pin "D22") (pinfunction "D22_D22") (pintype "bidirectional"))
      (node (ref "U5") (pin "10") (pinfunction "SCL_10") (pintype "input"))
    )
    (net (code "65") (name "SDA") (class "Default")
      (node (ref "IC5") (pin "13") (pinfunction "SDA_13") (pintype "bidirectional"))
      (node (ref "R18") (pin "1") (pinfunction "1_1") (pintype "passive"))
      (node (ref "U$3") (pin "D21") (pinfunction "D21_D21") (pintype "bidirectional"))
      (node (ref "U5") (pin "9") (pinfunction "SDA_9") (pintype "bidirectional"))
    )
    (net (code "66") (name "TANK_SENSOR") (class "Default")
      (node (ref "IC5") (pin "21") (pinfunction "GPA0_21") (pintype "bidirectional"))
      (node (ref "R26") (pin "2") (pinfunction "2_2") (pintype "passive"))
      (node (ref "TANK_SENSOR") (pin "2") (pinfunction "2_2") (pintype "passive"))
    )
    (net (code "67") (name "TEMP_BOILER") (class "Default")
      (node (ref "TEMP_BOILER") (pin "2") (pinfunction "2_2") (pintype "passive"))
      (node (ref "U$3") (pin "D19") (pinfunction "D19_D19") (pintype "bidirectional"))
    )
    (net (code "68") (name "TEMP_BU") (class "Default")
      (node (ref "TEMP_BU") (pin "2") (pinfunction "2_2") (pintype "passive"))
      (node (ref "U$3") (pin "D4") (pinfunction "D4_D4") (pintype "bidirectional"))
    )
    (net (code "69") (name "TEMP_TUBE") (class "Default")
      (node (ref "TEMP_TUBE") (pin "2") (pinfunction "2_2") (pintype "passive"))
      (node (ref "U$3") (pin "D18") (pinfunction "D18_D18") (pintype "bidirectional"))
    )
    (net (code "70") (name "unconnected-(IC1-CV-Pad5)") (class "Default")
      (node (ref "IC1") (pin "5") (pinfunction "CV_5") (pintype "input"))
    )
    (net (code "71") (name "unconnected-(IC1-DIS-Pad7)") (class "Default")
      (node (ref "IC1") (pin "7") (pinfunction "DIS_7") (pintype "input"))
    )
    (net (code "72") (name "unconnected-(IC5-INTA-Pad20)") (class "Default")
      (node (ref "IC5") (pin "20") (pinfunction "INTA_20") (pintype "output"))
    )
    (net (code "73") (name "unconnected-(IC5-INTB-Pad19)") (class "Default")
      (node (ref "IC5") (pin "19") (pinfunction "INTB_19") (pintype "output"))
    )
    (net (code "74") (name "unconnected-(U$2-VINB+-Pad5)") (class "Default")
      (node (ref "U$2") (pin "5") (pinfunction "VINB+_5") (pintype "input"))
    )
    (net (code "75") (name "unconnected-(U$2-VINB--Pad6)") (class "Default")
      (node (ref "U$2") (pin "6") (pinfunction "VINB-_6") (pintype "input"))
    )
    (net (code "76") (name "unconnected-(U$2-VOUTB-Pad7)") (class "Default")
      (node (ref "U$2") (pin "7") (pinfunction "VOUTB_7") (pintype "output"))
    )
    (net (code "77") (name "unconnected-(U$3-PadCLK)") (class "Default")
      (node (ref "U$3") (pin "CLK") (pinfunction "CLK_CLK") (pintype "bidirectional"))
    )
    (net (code "78") (name "unconnected-(U$3-PadCMD)") (class "Default")
      (node (ref "U$3") (pin "CMD") (pinfunction "CMD_CMD") (pintype "bidirectional"))
    )
    (net (code "79") (name "unconnected-(U$3-PadEN)") (class "Default")
      (node (ref "U$3") (pin "EN") (pinfunction "EN_EN") (pintype "bidirectional"))
    )
    (net (code "80") (name "unconnected-(U$3-PadSD0)") (class "Default")
      (node (ref "U$3") (pin "SD0") (pinfunction "SD0_SD0") (pintype "bidirectional"))
    )
    (net (code "81") (name "unconnected-(U$3-PadSD1)") (class "Default")
      (node (ref "U$3") (pin "SD1") (pinfunction "SD1_SD1") (pintype "bidirectional"))
    )
    (net (code "82") (name "unconnected-(U$3-PadSD2)") (class "Default")
      (node (ref "U$3") (pin "SD2") (pinfunction "SD2_SD2") (pintype "bidirectional"))
    )
    (net (code "83") (name "unconnected-(U$3-PadSD3)") (class "Default")
      (node (ref "U$3") (pin "SD3") (pinfunction "SD3_SD3") (pintype "bidirectional"))
    )
    (net (code "84") (name "unconnected-(U$3-PadVN)") (class "Default")
      (node (ref "U$3") (pin "VN") (pinfunction "VN_VN") (pintype "bidirectional"))
    )
    (net (code "85") (name "unconnected-(U$3-PadVP)") (class "Default")
      (node (ref "U$3") (pin "VP") (pinfunction "VP_VP") (pintype "bidirectional"))
    )
  )
)
